# noise_lev.net
KiCad netlist of a schematic drawn in EAGLE
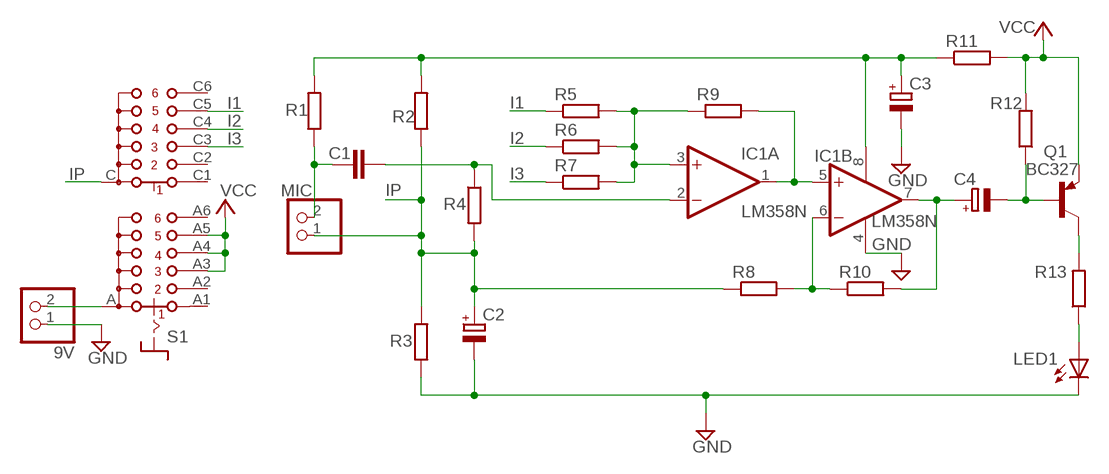
[diagram p0: schematic, sheet 1]

(export (version "E")
  (design (tool "Eeschema 10.0.6"))
  (components
    (comp (ref "9V")
      (value "PINHD-1X2")
      (footprint "eagle-import:1X02")
      (libsource (lib "eagle-import") (part "PINHD-1X2"))
    )
    (comp (ref "C1")
      (value "C-EU025-025X050")
      (footprint "eagle-import:C025-025X050")
      (libsource (lib "eagle-import") (part "C-EU025-025X050"))
    )
    (comp (ref "C2")
      (value "CPOL-EUE2.5-5")
      (footprint "eagle-import:E2,5-5")
      (libsource (lib "eagle-import") (part "CPOL-EUE2.5-5"))
    )
    (comp (ref "C3")
      (value "CPOL-EUE5-10.5")
      (footprint "eagle-import:E5-10,5")
      (libsource (lib "eagle-import") (part "CPOL-EUE5-10.5"))
    )
    (comp (ref "C4")
      (value "CPOL-EUE2.5-5")
      (footprint "eagle-import:E2,5-5")
      (libsource (lib "eagle-import") (part "CPOL-EUE2.5-5"))
    )
    (comp (ref "IC1")
      (value "LM358N")
      (footprint "eagle-import:DIL08")
      (libsource (lib "eagle-import") (part "LM358N"))
    )
    (comp (ref "LED1")
      (value "LED5MM")
      (footprint "eagle-import:LED5MM")
      (libsource (lib "eagle-import") (part "LED5MM"))
    )
    (comp (ref "MIC")
      (value "PINHD-1X2")
      (footprint "eagle-import:1X02")
      (libsource (lib "eagle-import") (part "PINHD-1X2"))
    )
    (comp (ref "Q1")
      (value "BC327")
      (footprint "eagle-import:TO92-EBC")
      (libsource (lib "eagle-import") (part "BC327"))
    )
    (comp (ref "R1")
      (value "R-EU_0207/10")
      (footprint "eagle-import:0207_10")
      (libsource (lib "eagle-import") (part "R-EU_0207/10"))
    )
    (comp (ref "R2")
      (value "R-EU_0207/10")
      (footprint "eagle-import:0207_10")
      (libsource (lib "eagle-import") (part "R-EU_0207/10"))
    )
    (comp (ref "R3")
      (value "R-EU_0207/10")
      (footprint "eagle-import:0207_10")
      (libsource (lib "eagle-import") (part "R-EU_0207/10"))
    )
    (comp (ref "R4")
      (value "R-EU_0207/10")
      (footprint "eagle-import:0207_10")
      (libsource (lib "eagle-import") (part "R-EU_0207/10"))
    )
    (comp (ref "R5")
      (value "R-EU_0207/10")
      (footprint "eagle-import:0207_10")
      (libsource (lib "eagle-import") (part "R-EU_0207/10"))
    )
    (comp (ref "R6")
      (value "R-EU_0207/10")
      (footprint "eagle-import:0207_10")
      (libsource (lib "eagle-import") (part "R-EU_0207/10"))
    )
    (comp (ref "R7")
      (value "R-EU_0207/10")
      (footprint "eagle-import:0207_10")
      (libsource (lib "eagle-import") (part "R-EU_0207/10"))
    )
    (comp (ref "R8")
      (value "R-EU_0207/10")
      (footprint "eagle-import:0207_10")
      (libsource (lib "eagle-import") (part "R-EU_0207/10"))
    )
    (comp (ref "R9")
      (value "R-EU_0207/10")
      (footprint "eagle-import:0207_10")
      (libsource (lib "eagle-import") (part "R-EU_0207/10"))
    )
    (comp (ref "R10")
      (value "R-EU_0207/10")
      (footprint "eagle-import:0207_10")
      (libsource (lib "eagle-import") (part "R-EU_0207/10"))
    )
    (comp (ref "R11")
      (value "R-EU_0207/10")
      (footprint "eagle-import:0207_10")
      (libsource (lib "eagle-import") (part "R-EU_0207/10"))
    )
    (comp (ref "R12")
      (value "R-EU_0207/10")
      (footprint "eagle-import:0207_10")
      (libsource (lib "eagle-import") (part "R-EU_0207/10"))
    )
    (comp (ref "R13")
      (value "R-EU_0207/10")
      (footprint "eagle-import:0207_10")
      (libsource (lib "eagle-import") (part "R-EU_0207/10"))
    )
    (comp (ref "S1")
      (value "CK102X06")
      (footprint "eagle-import:CK102X06")
      (libsource (lib "eagle-import") (part "CK102X06"))
    )
  )
  (nets
    (net (code "1") (name "/I1") (class "Default")
      (node (ref "R5") (pin "1") (pinfunction "1_1") (pintype "passive"))
      (node (ref "S1") (pin "C5") (pinfunction "C5_C5") (pintype "passive"))
    )
    (net (code "2") (name "/I2") (class "Default")
      (node (ref "R6") (pin "1") (pinfunction "1_1") (pintype "passive"))
      (node (ref "S1") (pin "C4") (pinfunction "C4_C4") (pintype "passive"))
    )
    (net (code "3") (name "/I3") (class "Default")
      (node (ref "R7") (pin "1") (pinfunction "1_1") (pintype "passive"))
      (node (ref "S1") (pin "C3") (pinfunction "C3_C3") (pintype "passive"))
    )
    (net (code "4") (name "/IP") (class "Default")
      (node (ref "C2") (pin "+") (pinfunction "+_+") (pintype "passive"))
      (node (ref "MIC") (pin "1") (pinfunction "1_1") (pintype "passive"))
      (node (ref "R2") (pin "1") (pinfunction "1_1") (pintype "passive"))
      (node (ref "R3") (pin "2") (pinfunction "2_2") (pintype "passive"))
      (node (ref "R4") (pin "2") (pinfunction "2_2") (pintype "passive"))
      (node (ref "R8") (pin "1") (pinfunction "1_1") (pintype "passive"))
      (node (ref "S1") (pin "C") (pinfunction "C_C") (pintype "passive"))
    )
    (net (code "5") (name "GND") (class "Default")
      (node (ref "9V") (pin "1") (pinfunction "1_1") (pintype "passive"))
      (node (ref "C2") (pin "-") (pinfunction "-_-") (pintype "passive"))
      (node (ref "C3") (pin "-") (pinfunction "-_-") (pintype "passive"))
      (node (ref "IC1") (pin "4") (pinfunction "V-_4") (pintype "power_in"))
      (node (ref "LED1") (pin "K") (pinfunction "C_K") (pintype "passive"))
      (node (ref "R3") (pin "1") (pinfunction "1_1") (pintype "passive"))
    )
    (net (code "6") (name "Net-(9V-Pad2)") (class "Default")
      (node (ref "9V") (pin "2") (pinfunction "2_2") (pintype "passive"))
      (node (ref "S1") (pin "A") (pinfunction "A_A") (pintype "passive"))
    )
    (net (code "7") (name "Net-(C1-Pad1)") (class "Default")
      (node (ref "C1") (pin "1") (pinfunction "1_1") (pintype "passive"))
      (node (ref "MIC") (pin "2") (pinfunction "2_2") (pintype "passive"))
      (node (ref "R1") (pin "1") (pinfunction "1_1") (pintype "passive"))
    )
    (net (code "8") (name "Net-(C4-Pad-)") (class "Default")
      (node (ref "C4") (pin "-") (pinfunction "-_-") (pintype "passive"))
      (node (ref "Q1") (pin "B") (pinfunction "B_B") (pintype "passive"))
      (node (ref "R12") (pin "1") (pinfunction "1_1") (pintype "passive"))
    )
    (net (code "9") (name "Net-(IC1A-+IN)") (class "Default")
      (node (ref "IC1") (pin "3") (pinfunction "+IN_3") (pintype "input"))
      (node (ref "R5") (pin "2") (pinfunction "2_2") (pintype "passive"))
      (node (ref "R6") (pin "2") (pinfunction "2_2") (pintype "passive"))
      (node (ref "R7") (pin "2") (pinfunction "2_2") (pintype "passive"))
      (node (ref "R9") (pin "1") (pinfunction "1_1") (pintype "passive"))
    )
    (net (code "10") (name "Net-(IC1A--IN)") (class "Default")
      (node (ref "C1") (pin "2") (pinfunction "2_2") (pintype "passive"))
      (node (ref "IC1") (pin "2") (pinfunction "-IN_2") (pintype "input"))
      (node (ref "R4") (pin "1") (pinfunction "1_1") (pintype "passive"))
    )
    (net (code "11") (name "Net-(IC1A-OUT)") (class "Default")
      (node (ref "IC1") (pin "1") (pinfunction "OUT_1") (pintype "output"))
      (node (ref "IC1") (pin "5") (pinfunction "+IN_5") (pintype "input"))
      (node (ref "R9") (pin "2") (pinfunction "2_2") (pintype "passive"))
    )
    (net (code "12") (name "Net-(IC1B--IN)") (class "Default")
      (node (ref "IC1") (pin "6") (pinfunction "-IN_6") (pintype "input"))
      (node (ref "R10") (pin "1") (pinfunction "1_1") (pintype "passive"))
      (node (ref "R8") (pin "2") (pinfunction "2_2") (pintype "passive"))
    )
    (net (code "13") (name "Net-(IC1B-OUT)") (class "Default")
      (node (ref "C4") (pin "+") (pinfunction "+_+") (pintype "passive"))
      (node (ref "IC1") (pin "7") (pinfunction "OUT_7") (pintype "output"))
      (node (ref "R10") (pin "2") (pinfunction "2_2") (pintype "passive"))
    )
    (net (code "14") (name "Net-(IC1C-V+)") (class "Default")
      (node (ref "C3") (pin "+") (pinfunction "+_+") (pintype "passive"))
      (node (ref "IC1") (pin "8") (pinfunction "V+_8") (pintype "power_in"))
      (node (ref "R1") (pin "2") (pinfunction "2_2") (pintype "passive"))
      (node (ref "R11") (pin "1") (pinfunction "1_1") (pintype "passive"))
      (node (ref "R2") (pin "2") (pinfunction "2_2") (pintype "passive"))
    )
    (net (code "15") (name "Net-(LED1-PadA)") (class "Default")
      (node (ref "LED1") (pin "A") (pinfunction "A_A") (pintype "passive"))
      (node (ref "R13") (pin "1") (pinfunction "1_1") (pintype "passive"))
    )
    (net (code "16") (name "Net-(Q1-PadC)") (class "Default")
      (node (ref "Q1") (pin "C") (pinfunction "C_C") (pintype "passive"))
      (node (ref "R13") (pin "2") (pinfunction "2_2") (pintype "passive"))
    )
    (net (code "17") (name "VCC") (class "Default")
      (node (ref "Q1") (pin "E") (pinfunction "E_E") (pintype "passive"))
      (node (ref "R11") (pin "2") (pinfunction "2_2") (pintype "passive"))
      (node (ref "R12") (pin "2") (pinfunction "2_2") (pintype "passive"))
      (node (ref "S1") (pin "A3") (pinfunction "A3_A3") (pintype "passive"))
      (node (ref "S1") (pin "A4") (pinfunction "A4_A4") (pintype "passive"))
      (node (ref "S1") (pin "A5") (pinfunction "A5_A5") (pintype "passive"))
    )
    (net (code "18") (name "unconnected-(S1-PadA1)") (class "Default")
      (node (ref "S1") (pin "A1") (pinfunction "A1_A1") (pintype "passive"))
    )
    (net (code "19") (name "unconnected-(S1-PadA2)") (class "Default")
      (node (ref "S1") (pin "A2") (pinfunction "A2_A2") (pintype "passive"))
    )
    (net (code "20") (name "unconnected-(S1-PadA6)") (class "Default")
      (node (ref "S1") (pin "A6") (pinfunction "A6_A6") (pintype "passive"))
    )
    (net (code "21") (name "unconnected-(S1-PadC1)") (class "Default")
      (node (ref "S1") (pin "C1") (pinfunction "C1_C1") (pintype "passive"))
    )
    (net (code "22") (name "unconnected-(S1-PadC2)") (class "Default")
      (node (ref "S1") (pin "C2") (pinfunction "C2_C2") (pintype "passive"))
    )
    (net (code "23") (name "unconnected-(S1-PadC6)") (class "Default")
      (node (ref "S1") (pin "C6") (pinfunction "C6_C6") (pintype "passive"))
    )
  )
)
